# Quad_SPI_Memory.net
KiCad netlist of a schematic drawn in Altium Designer
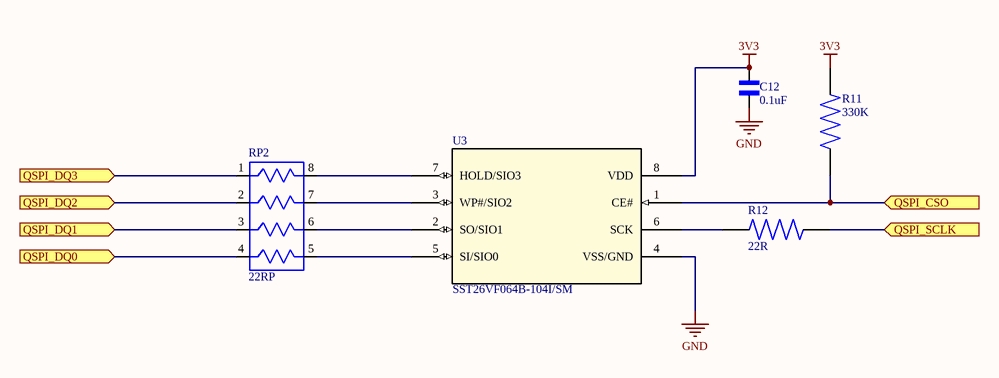
[diagram p0: Quad_SPI_Memory.SchDoc]

(export (version "E")
  (design (tool "Eeschema 10.0.6"))
  (components
    (comp (ref "C12")
      (value "0.1uF")
      (footprint "C0402")
      (description "CAP CER 0.1UF 6.3V X5R 01005")
      (fields
        (field (name "MANUFACTURER") "Murata")
        (field (name "MANUFACTURER PART NUMBER") "GRM022R60J104KE15L")
      )
      (libsource (lib "nnts") (part "GRM022R60J104KE15L"))
    )
    (comp (ref "R11")
      (value "330K")
      (footprint "R0603 Vishay")
      (fields
        (field (name "MANUFACTURER") "Vishay")
        (field (name "MANUFACTURER PART NUMBER") "CRCW0201330KFNED")
        (field (name "TOLERANCE") "1%")
      )
      (libsource (lib "nnts") (part "CRCW0201330KFNED"))
    )
    (comp (ref "R12")
      (value "22R")
      (footprint "R0402 Vishay")
      (description "VISHAY - CRCW040222R0FKED. - Resistor Case Style:0402 [1005 Metric], 22ohm")
      (fields
        (field (name "MANUFACTURER") "Vishay")
        (field (name "MANUFACTURER PART NUMBER") "CRCW040222R0FKED")
      )
      (libsource (lib "nnts") (part "CRCW040222R0FKED"))
    )
    (comp (ref "RP2")
      (value "22RP")
      (footprint "RESCAXS50P200X100X55-8N")
      (description "RES ARRAY 4 RES 22 OHM 0804")
      (fields
        (field (name "MANUFACTURER") "Yageo")
        (field (name "MANUFACTURER PART NUMBER") "YC124-JR-0722RL")
      )
      (libsource (lib "nnts") (part "YC124-JR-0722RL"))
    )
    (comp (ref "U3")
      (value "SST26VF064B-104I/SM")
      (footprint "SST26VF064B-104V/SM")
      (description "Quad SPI Memory; Flash Serial 3V 64Mbit 64M x 1Bit 8-Pin SOIJ")
      (fields (field (name "COPYRIGHT") "Copyright (C) 2018 Accelerated Designs. All rights reserved"))
      (libsource (lib "nnts") (part "SST26VF064B-104I/SM"))
    )
  )
  (nets
    (net (code "1") (name "/QSPI_CSO") (class "Default")
      (node (ref "R11") (pin "1") (pinfunction "1_1") (pintype "passive"))
      (node (ref "U3") (pin "1") (pinfunction "CE#_1") (pintype "input"))
    )
    (net (code "2") (name "/QSPI_DQ0") (class "Default")
      (node (ref "RP2") (pin "4") (pinfunction "4_4") (pintype "passive"))
    )
    (net (code "3") (name "/QSPI_DQ1") (class "Default")
      (node (ref "RP2") (pin "3") (pinfunction "3_3") (pintype "passive"))
    )
    (net (code "4") (name "/QSPI_DQ2") (class "Default")
      (node (ref "RP2") (pin "2") (pinfunction "2_2") (pintype "passive"))
    )
    (net (code "5") (name "/QSPI_DQ3") (class "Default")
      (node (ref "RP2") (pin "1") (pinfunction "1_1") (pintype "passive"))
    )
    (net (code "6") (name "/QSPI_SCLK") (class "Default")
      (node (ref "R12") (pin "2") (pinfunction "2_2") (pintype "passive"))
    )
    (net (code "7") (name "3V3") (class "Default")
      (node (ref "C12") (pin "2") (pinfunction "2_2") (pintype "passive"))
      (node (ref "R11") (pin "2") (pinfunction "2_2") (pintype "passive"))
      (node (ref "U3") (pin "8") (pinfunction "VDD_8") (pintype "power_in"))
    )
    (net (code "8") (name "GND") (class "Default")
      (node (ref "C12") (pin "1") (pinfunction "1_1") (pintype "passive"))
      (node (ref "U3") (pin "4") (pinfunction "VSS/GND_4") (pintype "passive"))
    )
    (net (code "9") (name "Net-(U3-HOLD{slash}SIO3)") (class "Default")
      (node (ref "RP2") (pin "8") (pinfunction "8_8") (pintype "passive"))
      (node (ref "U3") (pin "7") (pinfunction "HOLD/SIO3_7") (pintype "bidirectional"))
    )
    (net (code "10") (name "Net-(U3-SCK)") (class "Default")
      (node (ref "R12") (pin "1") (pinfunction "1_1") (pintype "passive"))
      (node (ref "U3") (pin "6") (pinfunction "SCK_6") (pintype "passive"))
    )
    (net (code "11") (name "Net-(U3-SI{slash}SIO0)") (class "Default")
      (node (ref "RP2") (pin "5") (pinfunction "5_5") (pintype "passive"))
      (node (ref "U3") (pin "5") (pinfunction "SI/SIO0_5") (pintype "bidirectional"))
    )
    (net (code "12") (name "Net-(U3-SO{slash}SIO1)") (class "Default")
      (node (ref "RP2") (pin "6") (pinfunction "6_6") (pintype "passive"))
      (node (ref "U3") (pin "2") (pinfunction "SO/SIO1_2") (pintype "bidirectional"))
    )
    (net (code "13") (name "Net-(U3-WP#{slash}SIO2)") (class "Default")
      (node (ref "RP2") (pin "7") (pinfunction "7_7") (pintype "passive"))
      (node (ref "U3") (pin "3") (pinfunction "WP#/SIO2_3") (pintype "bidirectional"))
    )
  )
)
